# TSOC_RS485_EM.net
KiCad netlist of a schematic drawn in EAGLE
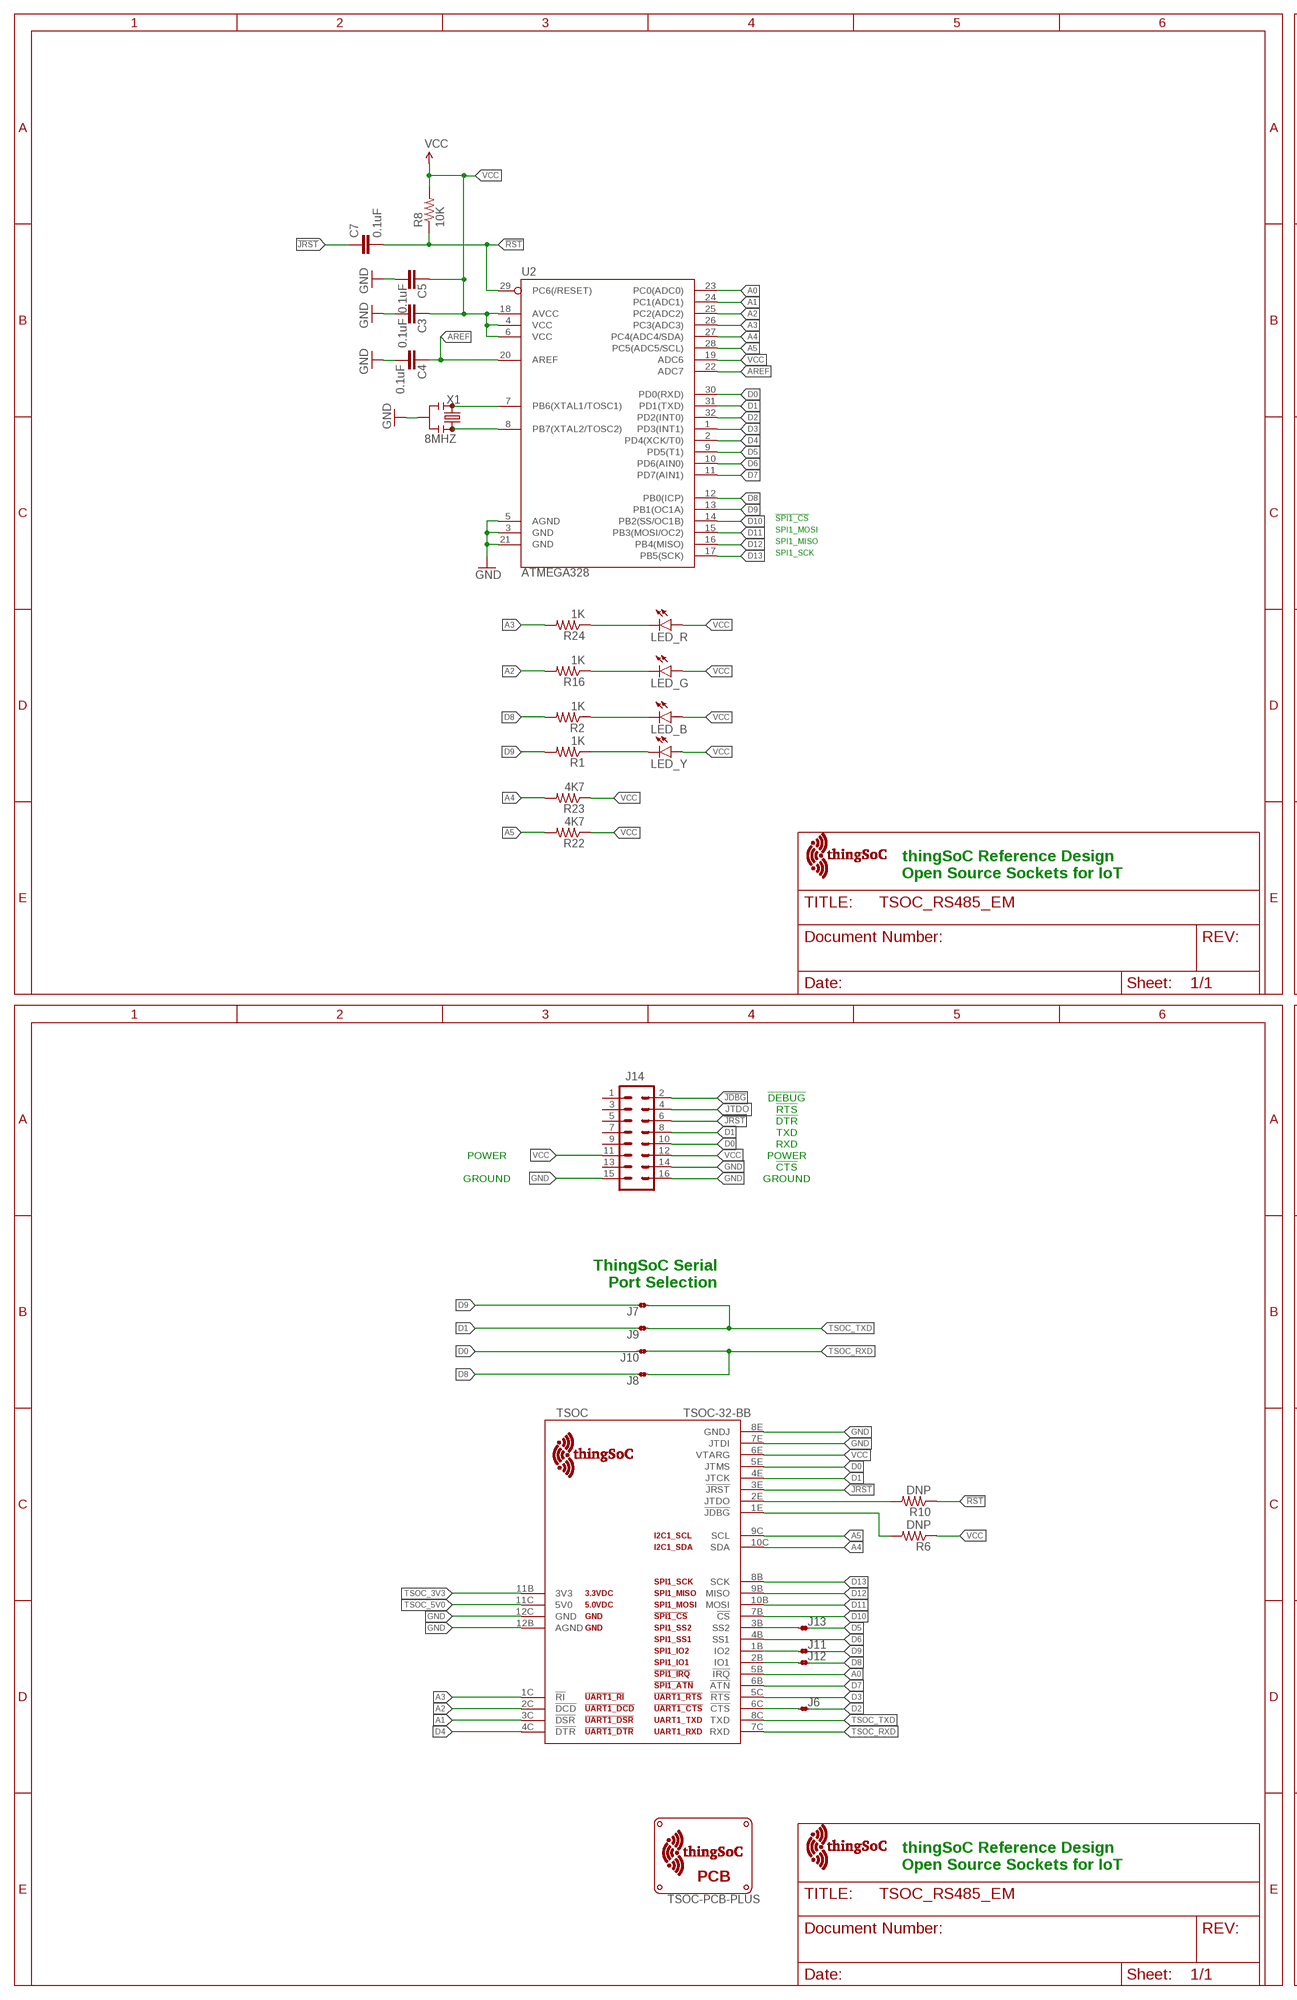
[diagram p0: schematic, sheet 1, part 1 of 2]
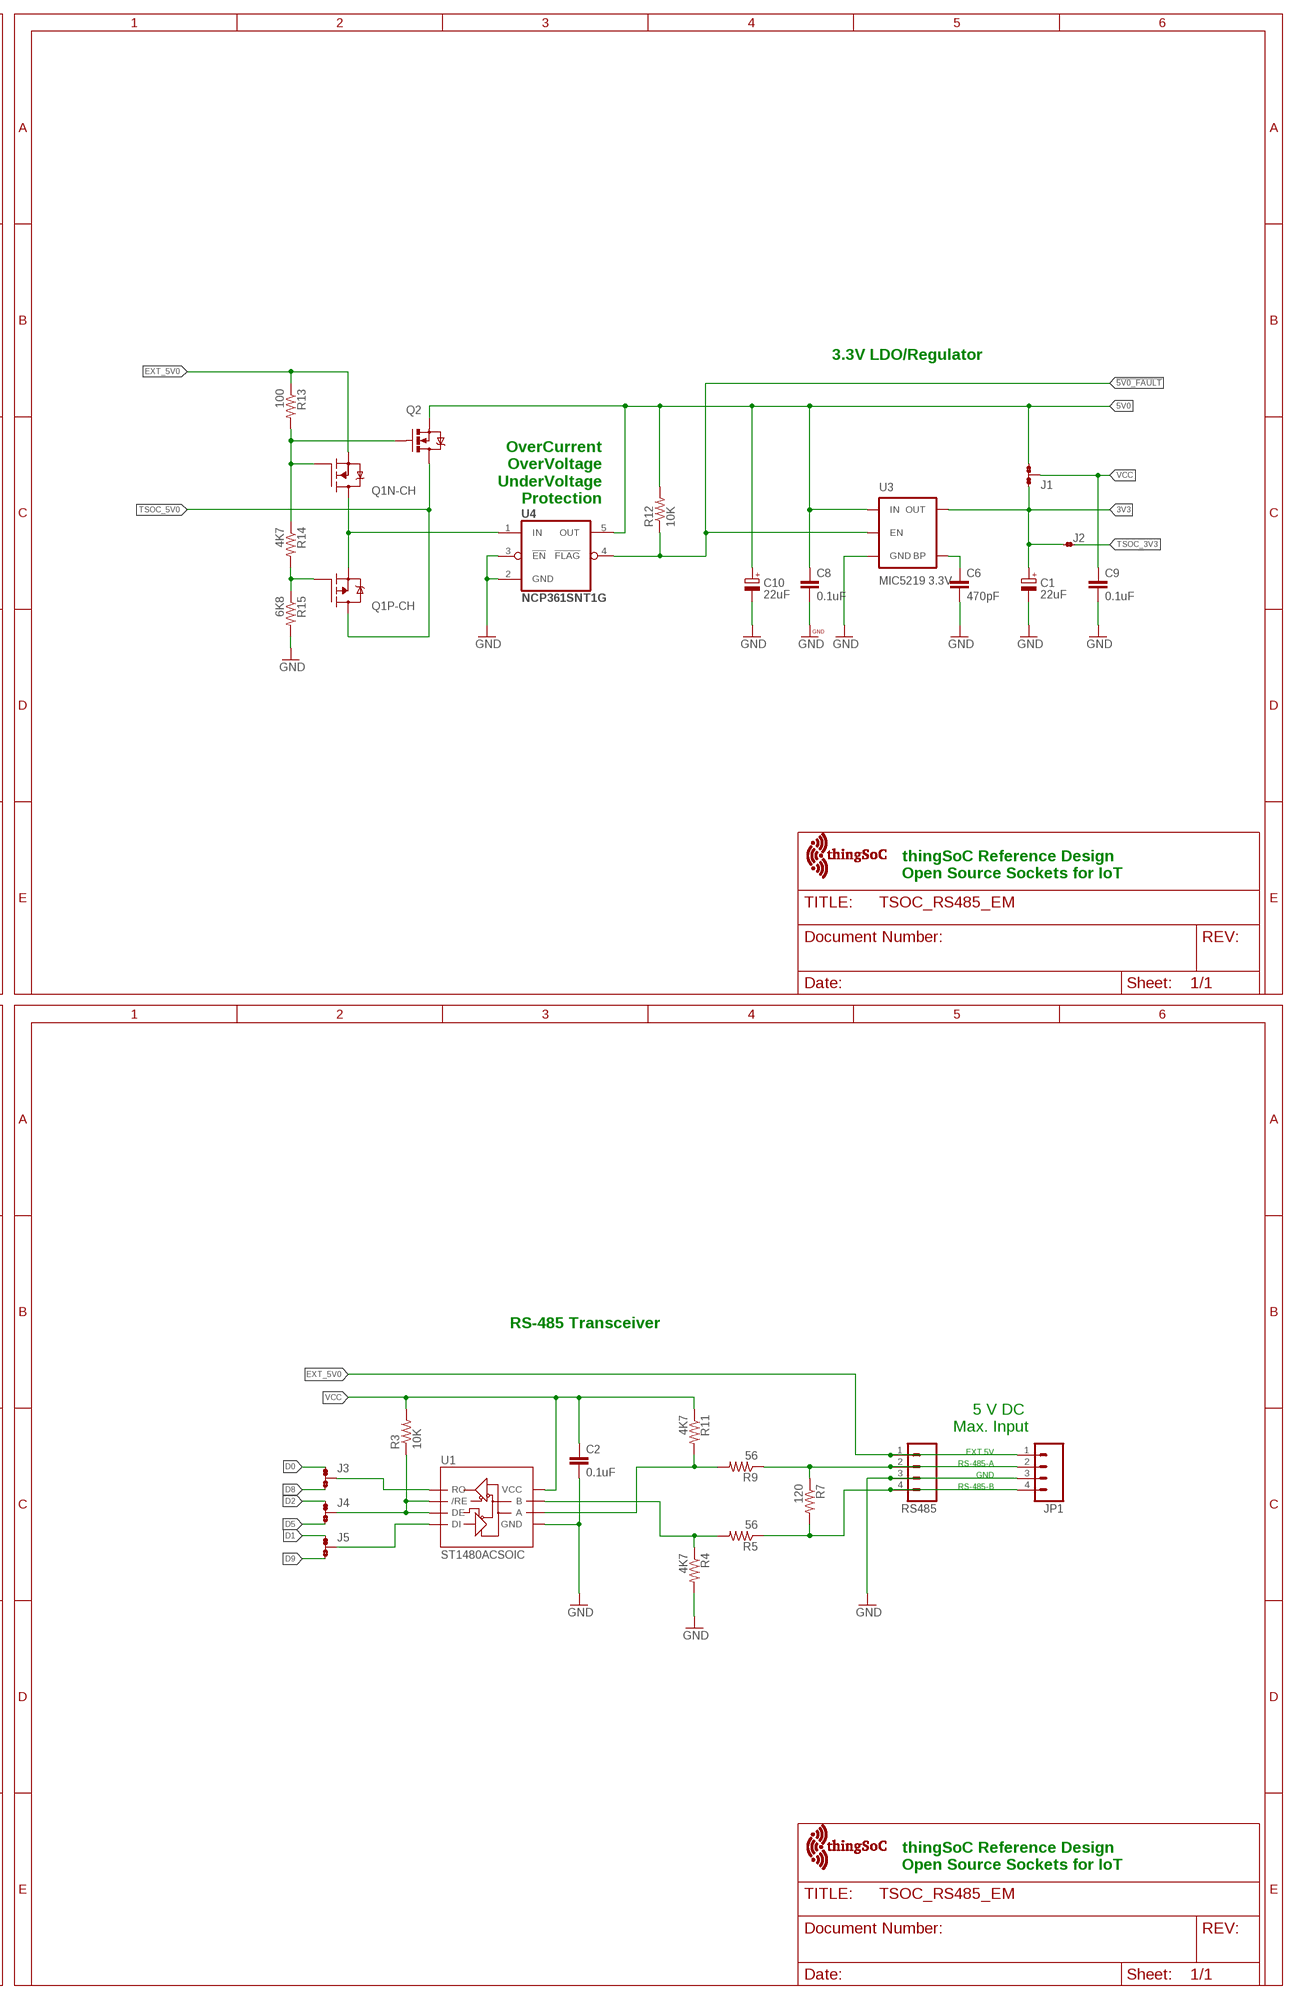
[diagram p1: schematic, sheet 1, part 2 of 2]

(export (version "E")
  (design (tool "Eeschema 10.0.6"))
  (components
    (comp (ref "C1")
      (value "22uF")
      (footprint "eagle-import:SMC_B")
      (libsource (lib "eagle-import") (part "CPOL-EUSMCB"))
    )
    (comp (ref "C2")
      (value "0.1uF")
      (footprint "eagle-import:EIA-0402")
      (libsource (lib "eagle-import") (part "CAPTYP"))
    )
    (comp (ref "C3")
      (value "0.1uF")
      (footprint "eagle-import:EIA-0402")
      (libsource (lib "eagle-import") (part "CAPTYP"))
    )
    (comp (ref "C4")
      (value "0.1uF")
      (footprint "eagle-import:EIA-0402")
      (libsource (lib "eagle-import") (part "CAPTYP"))
    )
    (comp (ref "C5")
      (value "0.1uF")
      (footprint "eagle-import:EIA-0402")
      (libsource (lib "eagle-import") (part "CAPTYP"))
    )
    (comp (ref "C6")
      (value "470pF")
      (footprint "eagle-import:EIA-0402")
      (libsource (lib "eagle-import") (part "CAPTYP"))
    )
    (comp (ref "C7")
      (value "0.1uF")
      (footprint "eagle-import:EIA-0402")
      (libsource (lib "eagle-import") (part "CAPTYP"))
    )
    (comp (ref "C8")
      (value "0.1uF")
      (footprint "eagle-import:EIA-0402")
      (libsource (lib "eagle-import") (part "CAPTYP"))
    )
    (comp (ref "C9")
      (value "0.1uF")
      (footprint "eagle-import:EIA-0402")
      (libsource (lib "eagle-import") (part "CAPTYP"))
    )
    (comp (ref "C10")
      (value "22uF")
      (footprint "eagle-import:SMC_B")
      (libsource (lib "eagle-import") (part "CPOL-EUSMCB"))
    )
    (comp (ref "J1")
      (value "JMP-3-1_2")
      (footprint "eagle-import:JMP-3-1_2")
      (libsource (lib "eagle-import") (part "JMP-3-1_2"))
    )
    (comp (ref "J2")
      (value "JMP-2-NC")
      (footprint "eagle-import:JMP-2-NC")
      (libsource (lib "eagle-import") (part "JMP-2-NC"))
    )
    (comp (ref "J3")
      (value "JMP-3-1_2")
      (footprint "eagle-import:JMP-3-1_2")
      (libsource (lib "eagle-import") (part "TSOC_RS485_EM_JMP-3-1_2"))
    )
    (comp (ref "J4")
      (value "JMP-3-1_2")
      (footprint "eagle-import:JMP-3-1_2")
      (libsource (lib "eagle-import") (part "TSOC_RS485_EM_JMP-3-1_2"))
    )
    (comp (ref "J5")
      (value "JMP-3-1_2")
      (footprint "eagle-import:JMP-3-1_2")
      (libsource (lib "eagle-import") (part "TSOC_RS485_EM_JMP-3-1_2"))
    )
    (comp (ref "J6")
      (value "JMP-2-NO")
      (footprint "eagle-import:JMP-2-NO")
      (libsource (lib "eagle-import") (part "JMP-2-NO"))
    )
    (comp (ref "J7")
      (value "JMP-2-NO")
      (footprint "eagle-import:JMP-2-NO")
      (libsource (lib "eagle-import") (part "JMP-2-NO"))
    )
    (comp (ref "J8")
      (value "JMP-2-NO")
      (footprint "eagle-import:JMP-2-NO")
      (libsource (lib "eagle-import") (part "JMP-2-NO"))
    )
    (comp (ref "J9")
      (value "JMP-2-NO")
      (footprint "eagle-import:JMP-2-NO")
      (libsource (lib "eagle-import") (part "JMP-2-NO"))
    )
    (comp (ref "J10")
      (value "JMP-2-NO")
      (footprint "eagle-import:JMP-2-NO")
      (libsource (lib "eagle-import") (part "JMP-2-NO"))
    )
    (comp (ref "J11")
      (value "JMP-2-NC")
      (footprint "eagle-import:JMP-2-NC")
      (libsource (lib "eagle-import") (part "JMP-2-NC"))
    )
    (comp (ref "J12")
      (value "JMP-2-NC")
      (footprint "eagle-import:JMP-2-NC")
      (libsource (lib "eagle-import") (part "JMP-2-NC"))
    )
    (comp (ref "J13")
      (value "JMP-2-NC")
      (footprint "eagle-import:JMP-2-NC")
      (libsource (lib "eagle-import") (part "JMP-2-NC"))
    )
    (comp (ref "J14")
      (value "M08X2")
      (footprint "eagle-import:2X8")
      (libsource (lib "eagle-import") (part "M08X2"))
    )
    (comp (ref "JP1")
      (value "M04PTH")
      (footprint "eagle-import:1X04")
      (libsource (lib "eagle-import") (part "M04PTH"))
    )
    (comp (ref "LED_B")
      (value "LED0603")
      (footprint "eagle-import:LED-0603")
      (libsource (lib "eagle-import") (part "LED0603"))
    )
    (comp (ref "LED_G")
      (value "LED0603")
      (footprint "eagle-import:LED-0603")
      (libsource (lib "eagle-import") (part "LED0603"))
    )
    (comp (ref "LED_R")
      (value "LED0603")
      (footprint "eagle-import:LED-0603")
      (libsource (lib "eagle-import") (part "LED0603"))
    )
    (comp (ref "LED_Y")
      (value "LED0603")
      (footprint "eagle-import:LED-0603")
      (libsource (lib "eagle-import") (part "LED0603"))
    )
    (comp (ref "Q1")
      (value "FDC6420C")
      (footprint "eagle-import:SOT95P280X110-6N")
      (libsource (lib "eagle-import") (part "FDC6420C"))
    )
    (comp (ref "Q2")
      (value "MOSFET-NCHANNELAO3404A")
      (footprint "eagle-import:SOT23-3")
      (libsource (lib "eagle-import") (part "MOSFET-NCHANNELAO3404A"))
    )
    (comp (ref "R1")
      (value "1K")
      (footprint "eagle-import:EIA-0402-MIN")
      (libsource (lib "eagle-import") (part "RESISTOR0402-MIN"))
    )
    (comp (ref "R2")
      (value "1K")
      (footprint "eagle-import:EIA-0402-MIN")
      (libsource (lib "eagle-import") (part "RESISTOR0402-MIN"))
    )
    (comp (ref "R3")
      (value "10K")
      (footprint "eagle-import:EIA-0402-MIN")
      (libsource (lib "eagle-import") (part "RESISTOR0402-MIN"))
    )
    (comp (ref "R4")
      (value "4K7")
      (footprint "eagle-import:EIA-0402-MIN")
      (libsource (lib "eagle-import") (part "RESISTOR0402-MIN"))
    )
    (comp (ref "R5")
      (value "56")
      (footprint "eagle-import:EIA-0402-MIN")
      (libsource (lib "eagle-import") (part "RESISTOR0402-MIN"))
    )
    (comp (ref "R6")
      (value "DNP")
      (footprint "eagle-import:EIA-0402-MIN")
      (libsource (lib "eagle-import") (part "RESISTOR0402-MIN"))
    )
    (comp (ref "R7")
      (value "120")
      (footprint "eagle-import:EIA-0402-MIN")
      (libsource (lib "eagle-import") (part "RESISTOR0402-MIN"))
    )
    (comp (ref "R8")
      (value "10K")
      (footprint "eagle-import:EIA-0402-MIN")
      (libsource (lib "eagle-import") (part "RESISTOR0402-MIN"))
    )
    (comp (ref "R9")
      (value "56")
      (footprint "eagle-import:EIA-0402-MIN")
      (libsource (lib "eagle-import") (part "RESISTOR0402-MIN"))
    )
    (comp (ref "R10")
      (value "DNP")
      (footprint "eagle-import:EIA-0402-MIN")
      (libsource (lib "eagle-import") (part "RESISTOR0402-MIN"))
    )
    (comp (ref "R11")
      (value "4K7")
      (footprint "eagle-import:EIA-0402-MIN")
      (libsource (lib "eagle-import") (part "RESISTOR0402-MIN"))
    )
    (comp (ref "R12")
      (value "10K")
      (footprint "eagle-import:EIA-0402-MIN")
      (libsource (lib "eagle-import") (part "RESISTOR0402-MIN"))
    )
    (comp (ref "R13")
      (value "100")
      (footprint "eagle-import:EIA-0402-MIN")
      (libsource (lib "eagle-import") (part "RESISTOR0402-MIN"))
    )
    (comp (ref "R14")
      (value "4K7")
      (footprint "eagle-import:EIA-0402-MIN")
      (libsource (lib "eagle-import") (part "RESISTOR0402-MIN"))
    )
    (comp (ref "R15")
      (value "6K8")
      (footprint "eagle-import:EIA-0402-MIN")
      (libsource (lib "eagle-import") (part "RESISTOR0402-MIN"))
    )
    (comp (ref "R16")
      (value "1K")
      (footprint "eagle-import:EIA-0402-MIN")
      (libsource (lib "eagle-import") (part "RESISTOR0402-MIN"))
    )
    (comp (ref "R22")
      (value "4K7")
      (footprint "eagle-import:EIA-0402-MIN")
      (libsource (lib "eagle-import") (part "RESISTOR0402-MIN"))
    )
    (comp (ref "R23")
      (value "4K7")
      (footprint "eagle-import:EIA-0402-MIN")
      (libsource (lib "eagle-import") (part "RESISTOR0402-MIN"))
    )
    (comp (ref "R24")
      (value "1K")
      (footprint "eagle-import:EIA-0402-MIN")
      (libsource (lib "eagle-import") (part "RESISTOR0402-MIN"))
    )
    (comp (ref "RS485")
      (value "M04SCREW")
      (footprint "eagle-import:SCREWTERMINAL-3.5MM-4")
      (libsource (lib "eagle-import") (part "M04SCREW"))
    )
    (comp (ref "TSOC")
      (value "TSOC-32-BB")
      (footprint "eagle-import:TSOC-BB-S32")
      (libsource (lib "eagle-import") (part "TSOC-32-BB"))
    )
    (comp (ref "U$3")
      (value "TSOC-PCB-PLUS")
      (footprint "eagle-import:TSOC-BB-BRD-PLUS")
      (libsource (lib "eagle-import") (part "TSOC-PCB-PLUS"))
    )
    (comp (ref "U$5")
      (value "TSOC-LOGO-SMALL")
      (footprint "eagle-import:TSOC-LOGO-SML")
      (libsource (lib "eagle-import") (part "TSOC-LOGO-SMALL"))
    )
    (comp (ref "U$6")
      (value "TSOC-LOGO-SMALL")
      (footprint "eagle-import:TSOC-LOGO-SML")
      (libsource (lib "eagle-import") (part "TSOC-LOGO-SMALL"))
    )
    (comp (ref "U$7")
      (value "TSOC-LOGO-SMALL")
      (footprint "eagle-import:TSOC-LOGO-SML")
      (libsource (lib "eagle-import") (part "TSOC-LOGO-SMALL"))
    )
    (comp (ref "U$8")
      (value "TSOC-LOGO-SMALL")
      (footprint "eagle-import:TSOC-LOGO-SML")
      (libsource (lib "eagle-import") (part "TSOC-LOGO-SMALL"))
    )
    (comp (ref "U1")
      (value "ST1480ACSOIC")
      (footprint "eagle-import:SO08")
      (libsource (lib "eagle-import") (part "ST1480ACSOIC"))
    )
    (comp (ref "U2")
      (value "ATMEGA328")
      (footprint "eagle-import:TQFP32-08")
      (libsource (lib "eagle-import") (part "ATMEGA168"))
    )
    (comp (ref "U3")
      (value "MIC5219 3.3V")
      (footprint "eagle-import:SOT23-5")
      (libsource (lib "eagle-import") (part "V_REG_MIC52193.3V"))
    )
    (comp (ref "U4")
      (value "NCP361SNT1G")
      (footprint "eagle-import:SOP95P275X110-5N")
      (libsource (lib "eagle-import") (part "NCP361SNT1G"))
    )
    (comp (ref "X1")
      (value "8MHZ")
      (footprint "eagle-import:RESONATOR-SMD")
      (libsource (lib "eagle-import") (part "RESONATOR8MHZ"))
    )
  )
  (nets
    (net (code "1") (name "/~{5V0_FAULT}") (class "Default")
      (node (ref "R12") (pin "1") (pinfunction "1_1") (pintype "passive"))
      (node (ref "U3") (pin "3") (pinfunction "EN_3") (pintype "input"))
      (node (ref "U4") (pin "4") (pinfunction "~{FLAG}_4") (pintype "input"))
    )
    (net (code "2") (name "/~{JDBG}") (class "Default")
      (node (ref "J14") (pin "2") (pinfunction "2_2") (pintype "passive"))
      (node (ref "R6") (pin "2") (pinfunction "2_2") (pintype "passive"))
      (node (ref "TSOC") (pin "1E") (pinfunction "~{JDBG}_1E") (pintype "bidirectional"))
    )
    (net (code "3") (name "/~{JRST}") (class "Default")
      (node (ref "C7") (pin "1") (pinfunction "1_1") (pintype "passive"))
      (node (ref "J14") (pin "6") (pinfunction "6_6") (pintype "passive"))
      (node (ref "TSOC") (pin "3E") (pinfunction "~{JRST}_3E") (pintype "bidirectional"))
    )
    (net (code "4") (name "/~{RST}") (class "Default")
      (node (ref "C7") (pin "2") (pinfunction "2_2") (pintype "passive"))
      (node (ref "R10") (pin "1") (pinfunction "1_1") (pintype "passive"))
      (node (ref "R8") (pin "1") (pinfunction "1_1") (pintype "passive"))
      (node (ref "U2") (pin "29") (pinfunction "PC6(/RESET)_29") (pintype "bidirectional"))
    )
    (net (code "5") (name "3V3") (class "Default")
      (node (ref "C1") (pin "+") (pinfunction "+_+") (pintype "passive"))
      (node (ref "J1") (pin "1") (pinfunction "1_1") (pintype "passive"))
      (node (ref "J2") (pin "1") (pinfunction "1_1") (pintype "passive"))
      (node (ref "U3") (pin "5") (pinfunction "OUT_5") (pintype "passive"))
    )
    (net (code "6") (name "5V0") (class "Default")
      (node (ref "C10") (pin "+") (pinfunction "+_+") (pintype "passive"))
      (node (ref "C8") (pin "1") (pinfunction "1_1") (pintype "passive"))
      (node (ref "J1") (pin "3") (pinfunction "3_3") (pintype "passive"))
      (node (ref "Q2") (pin "2") (pinfunction "S_2") (pintype "passive"))
      (node (ref "R12") (pin "2") (pinfunction "2_2") (pintype "passive"))
      (node (ref "U3") (pin "1") (pinfunction "IN_1") (pintype "input"))
      (node (ref "U4") (pin "5") (pinfunction "OUT_5") (pintype "output"))
    )
    (net (code "7") (name "A0") (class "Default")
      (node (ref "TSOC") (pin "5B") (pinfunction "~{IRQ}_5B") (pintype "bidirectional"))
      (node (ref "U2") (pin "23") (pinfunction "PC0(ADC0)_23") (pintype "bidirectional"))
    )
    (net (code "8") (name "A1") (class "Default")
      (node (ref "TSOC") (pin "3C") (pinfunction "~{DSR}_3C") (pintype "bidirectional"))
      (node (ref "U2") (pin "24") (pinfunction "PC1(ADC1)_24") (pintype "bidirectional"))
    )
    (net (code "9") (name "A2") (class "Default")
      (node (ref "R16") (pin "2") (pinfunction "2_2") (pintype "passive"))
      (node (ref "TSOC") (pin "2C") (pinfunction "~{DCD}_2C") (pintype "bidirectional"))
      (node (ref "U2") (pin "25") (pinfunction "PC2(ADC2)_25") (pintype "bidirectional"))
    )
    (net (code "10") (name "A3") (class "Default")
      (node (ref "R24") (pin "2") (pinfunction "2_2") (pintype "passive"))
      (node (ref "TSOC") (pin "1C") (pinfunction "~{RI}_1C") (pintype "bidirectional"))
      (node (ref "U2") (pin "26") (pinfunction "PC3(ADC3)_26") (pintype "bidirectional"))
    )
    (net (code "11") (name "A4") (class "Default")
      (node (ref "R23") (pin "2") (pinfunction "2_2") (pintype "passive"))
      (node (ref "TSOC") (pin "10C") (pinfunction "SDA_10C") (pintype "bidirectional"))
      (node (ref "U2") (pin "27") (pinfunction "PC4(ADC4/SDA)_27") (pintype "bidirectional"))
    )
    (net (code "12") (name "A5") (class "Default")
      (node (ref "R22") (pin "2") (pinfunction "2_2") (pintype "passive"))
      (node (ref "TSOC") (pin "9C") (pinfunction "SCL_9C") (pintype "bidirectional"))
      (node (ref "U2") (pin "28") (pinfunction "PC5(ADC5/SCL)_28") (pintype "bidirectional"))
    )
    (net (code "13") (name "AREF") (class "Default")
      (node (ref "C4") (pin "2") (pinfunction "2_2") (pintype "passive"))
      (node (ref "U2") (pin "20") (pinfunction "AREF_20") (pintype "bidirectional"))
      (node (ref "U2") (pin "22") (pinfunction "ADC7_22") (pintype "bidirectional"))
    )
    (net (code "14") (name "D0") (class "Default")
      (node (ref "J10") (pin "2") (pinfunction "2_2") (pintype "passive"))
      (node (ref "J14") (pin "10") (pinfunction "10_10") (pintype "passive"))
      (node (ref "J3") (pin "1") (pinfunction "1_1") (pintype "passive"))
      (node (ref "TSOC") (pin "5E") (pinfunction "JTMS_5E") (pintype "bidirectional"))
      (node (ref "U2") (pin "30") (pinfunction "PD0(RXD)_30") (pintype "bidirectional"))
    )
    (net (code "15") (name "D1") (class "Default")
      (node (ref "J14") (pin "8") (pinfunction "8_8") (pintype "passive"))
      (node (ref "J5") (pin "1") (pinfunction "1_1") (pintype "passive"))
      (node (ref "J9") (pin "2") (pinfunction "2_2") (pintype "passive"))
      (node (ref "TSOC") (pin "4E") (pinfunction "JTCK_4E") (pintype "bidirectional"))
      (node (ref "U2") (pin "31") (pinfunction "PD1(TXD)_31") (pintype "bidirectional"))
    )
    (net (code "16") (name "D2") (class "Default")
      (node (ref "J4") (pin "1") (pinfunction "1_1") (pintype "passive"))
      (node (ref "J6") (pin "2") (pinfunction "2_2") (pintype "passive"))
      (node (ref "U2") (pin "32") (pinfunction "PD2(INT0)_32") (pintype "bidirectional"))
    )
    (net (code "17") (name "D3") (class "Default")
      (node (ref "TSOC") (pin "5C") (pinfunction "~{RTS}_5C") (pintype "bidirectional"))
      (node (ref "U2") (pin "1") (pinfunction "PD3(INT1)_1") (pintype "bidirectional"))
    )
    (net (code "18") (name "D4") (class "Default")
      (node (ref "TSOC") (pin "4C") (pinfunction "~{DTR}_4C") (pintype "bidirectional"))
      (node (ref "U2") (pin "2") (pinfunction "PD4(XCK/T0)_2") (pintype "bidirectional"))
    )
    (net (code "19") (name "D5") (class "Default")
      (node (ref "J13") (pin "2") (pinfunction "2_2") (pintype "passive"))
      (node (ref "J4") (pin "3") (pinfunction "3_3") (pintype "passive"))
      (node (ref "U2") (pin "9") (pinfunction "PD5(T1)_9") (pintype "bidirectional"))
    )
    (net (code "20") (name "D6") (class "Default")
      (node (ref "TSOC") (pin "4B") (pinfunction "SS1_4B") (pintype "bidirectional"))
      (node (ref "U2") (pin "10") (pinfunction "PD6(AIN0)_10") (pintype "bidirectional"))
    )
    (net (code "21") (name "D7") (class "Default")
      (node (ref "TSOC") (pin "6B") (pinfunction "~{ATN}_6B") (pintype "bidirectional"))
      (node (ref "U2") (pin "11") (pinfunction "PD7(AIN1)_11") (pintype "bidirectional"))
    )
    (net (code "22") (name "D8") (class "Default")
      (node (ref "J12") (pin "2") (pinfunction "2_2") (pintype "passive"))
      (node (ref "J3") (pin "3") (pinfunction "3_3") (pintype "passive"))
      (node (ref "J8") (pin "2") (pinfunction "2_2") (pintype "passive"))
      (node (ref "R2") (pin "2") (pinfunction "2_2") (pintype "passive"))
      (node (ref "U2") (pin "12") (pinfunction "PB0(ICP)_12") (pintype "bidirectional"))
    )
    (net (code "23") (name "D9") (class "Default")
      (node (ref "J11") (pin "2") (pinfunction "2_2") (pintype "passive"))
      (node (ref "J5") (pin "3") (pinfunction "3_3") (pintype "passive"))
      (node (ref "J7") (pin "2") (pinfunction "2_2") (pintype "passive"))
      (node (ref "R1") (pin "2") (pinfunction "2_2") (pintype "passive"))
      (node (ref "U2") (pin "13") (pinfunction "PB1(OC1A)_13") (pintype "bidirectional"))
    )
    (net (code "24") (name "D10") (class "Default")
      (node (ref "TSOC") (pin "7B") (pinfunction "~{CS}_7B") (pintype "bidirectional"))
      (node (ref "U2") (pin "14") (pinfunction "PB2(SS/OC1B)_14") (pintype "bidirectional"))
    )
    (net (code "25") (name "D11") (class "Default")
      (node (ref "TSOC") (pin "10B") (pinfunction "MOSI_10B") (pintype "bidirectional"))
      (node (ref "U2") (pin "15") (pinfunction "PB3(MOSI/OC2)_15") (pintype "bidirectional"))
    )
    (net (code "26") (name "D12") (class "Default")
      (node (ref "TSOC") (pin "9B") (pinfunction "MISO_9B") (pintype "bidirectional"))
      (node (ref "U2") (pin "16") (pinfunction "PB4(MISO)_16") (pintype "bidirectional"))
    )
    (net (code "27") (name "D13") (class "Default")
      (node (ref "TSOC") (pin "8B") (pinfunction "SCK_8B") (pintype "bidirectional"))
      (node (ref "U2") (pin "17") (pinfunction "PB5(SCK)_17") (pintype "bidirectional"))
    )
    (net (code "28") (name "EXT_5V0") (class "Default")
      (node (ref "JP1") (pin "1") (pinfunction "1_1") (pintype "passive"))
      (node (ref "Q1") (pin "5") (pinfunction "S_5") (pintype "passive"))
      (node (ref "R13") (pin "1") (pinfunction "1_1") (pintype "passive"))
      (node (ref "RS485") (pin "1") (pinfunction "1_1") (pintype "passive"))
    )
    (net (code "29") (name "GND") (class "Default")
      (node (ref "C1") (pin "-") (pinfunction "-_-") (pintype "passive"))
      (node (ref "C10") (pin "-") (pinfunction "-_-") (pintype "passive"))
      (node (ref "C2") (pin "2") (pinfunction "2_2") (pintype "passive"))
      (node (ref "C3") (pin "1") (pinfunction "1_1") (pintype "passive"))
      (node (ref "C4") (pin "1") (pinfunction "1_1") (pintype "passive"))
      (node (ref "C5") (pin "1") (pinfunction "1_1") (pintype "passive"))
      (node (ref "C6") (pin "2") (pinfunction "2_2") (pintype "passive"))
      (node (ref "C8") (pin "2") (pinfunction "2_2") (pintype "passive"))
      (node (ref "C9") (pin "2") (pinfunction "2_2") (pintype "passive"))
      (node (ref "J14") (pin "14") (pinfunction "14_14") (pintype "passive"))
      (node (ref "J14") (pin "15") (pinfunction "15_15") (pintype "passive"))
      (node (ref "J14") (pin "16") (pinfunction "16_16") (pintype "passive"))
      (node (ref "JP1") (pin "3") (pinfunction "3_3") (pintype "passive"))
      (node (ref "R15") (pin "2") (pinfunction "2_2") (pintype "passive"))
      (node (ref "R4") (pin "2") (pinfunction "2_2") (pintype "passive"))
      (node (ref "RS485") (pin "3") (pinfunction "3_3") (pintype "passive"))
      (node (ref "TSOC") (pin "12B") (pinfunction "AGND_12B") (pintype "bidirectional"))
      (node (ref "TSOC") (pin "12C") (pinfunction "GND_12C") (pintype "bidirectional"))
      (node (ref "TSOC") (pin "7E") (pinfunction "JTDI_7E") (pintype "bidirectional"))
      (node (ref "TSOC") (pin "8E") (pinfunction "GNDJ_8E") (pintype "bidirectional"))
      (node (ref "U1") (pin "5") (pinfunction "GND_5") (pintype "bidirectional"))
      (node (ref "U2") (pin "21") (pinfunction "GND_21") (pintype "bidirectional"))
      (node (ref "U2") (pin "3") (pinfunction "GND_3") (pintype "bidirectional"))
      (node (ref "U2") (pin "5") (pinfunction "AGND_5") (pintype "bidirectional"))
      (node (ref "U3") (pin "2") (pinfunction "GND_2") (pintype "input"))
      (node (ref "U4") (pin "2") (pinfunction "GND_2") (pintype "passive"))
      (node (ref "U4") (pin "3") (pinfunction "~{EN}_3") (pintype "input"))
      (node (ref "X1") (pin "2") (pinfunction "2_2") (pintype "passive"))
    )
    (net (code "30") (name "JTDO") (class "Default")
      (node (ref "J14") (pin "4") (pinfunction "4_4") (pintype "passive"))
      (node (ref "R10") (pin "2") (pinfunction "2_2") (pintype "passive"))
      (node (ref "TSOC") (pin "2E") (pinfunction "JTDO_2E") (pintype "bidirectional"))
    )
    (net (code "31") (name "Net-(JP1-Pad2)") (class "Default")
      (node (ref "JP1") (pin "2") (pinfunction "2_2") (pintype "passive"))
      (node (ref "R7") (pin "1") (pinfunction "1_1") (pintype "passive"))
      (node (ref "R9") (pin "1") (pinfunction "1_1") (pintype "passive"))
      (node (ref "RS485") (pin "2") (pinfunction "2_2") (pintype "passive"))
    )
    (net (code "32") (name "Net-(JP1-Pad4)") (class "Default")
      (node (ref "JP1") (pin "4") (pinfunction "4_4") (pintype "passive"))
      (node (ref "R5") (pin "1") (pinfunction "1_1") (pintype "passive"))
      (node (ref "R7") (pin "2") (pinfunction "2_2") (pintype "passive"))
      (node (ref "RS485") (pin "4") (pinfunction "4_4") (pintype "passive"))
    )
    (net (code "33") (name "Net-(LED_B-PadC)") (class "Default")
      (node (ref "LED_B") (pin "C") (pinfunction "C_C") (pintype "passive"))
      (node (ref "R2") (pin "1") (pinfunction "1_1") (pintype "passive"))
    )
    (net (code "34") (name "Net-(LED_G-PadC)") (class "Default")
      (node (ref "LED_G") (pin "C") (pinfunction "C_C") (pintype "passive"))
      (node (ref "R16") (pin "1") (pinfunction "1_1") (pintype "passive"))
    )
    (net (code "35") (name "Net-(LED_R-PadC)") (class "Default")
      (node (ref "LED_R") (pin "C") (pinfunction "C_C") (pintype "passive"))
      (node (ref "R24") (pin "1") (pinfunction "1_1") (pintype "passive"))
    )
    (net (code "36") (name "Net-(LED_Y-PadC)") (class "Default")
      (node (ref "LED_Y") (pin "C") (pinfunction "C_C") (pintype "passive"))
      (node (ref "R1") (pin "1") (pinfunction "1_1") (pintype "passive"))
    )
    (net (code "37") (name "Net-(Q1A-D)") (class "Default")
      (node (ref "Q1") (pin "2") (pinfunction "S_2") (pintype "passive"))
      (node (ref "Q1") (pin "6") (pinfunction "D_6") (pintype "passive"))
      (node (ref "U4") (pin "1") (pinfunction "IN_1") (pintype "power_in"))
    )
    (net (code "38") (name "Net-(Q1A-G)") (class "Default")
      (node (ref "Q1") (pin "1") (pinfunction "G_1") (pintype "passive"))
      (node (ref "Q2") (pin "1") (pinfunction "G_1") (pintype "passive"))
      (node (ref "R13") (pin "2") (pinfunction "2_2") (pintype "passive"))
      (node (ref "R14") (pin "1") (pinfunction "1_1") (pintype "passive"))
    )
    (net (code "39") (name "Net-(Q1B-G)") (class "Default")
      (node (ref "Q1") (pin "3") (pinfunction "G_3") (pintype "passive"))
      (node (ref "R14") (pin "2") (pinfunction "2_2") (pintype "passive"))
      (node (ref "R15") (pin "1") (pinfunction "1_1") (pintype "passive"))
    )
    (net (code "40") (name "Net-(TSOC-IO1)") (class "Default")
      (node (ref "J12") (pin "1") (pinfunction "1_1") (pintype "passive"))
      (node (ref "TSOC") (pin "2B") (pinfunction "IO1_2B") (pintype "bidirectional"))
    )
    (net (code "41") (name "Net-(TSOC-IO2)") (class "Default")
      (node (ref "J11") (pin "1") (pinfunction "1_1") (pintype "passive"))
      (node (ref "TSOC") (pin "1B") (pinfunction "IO2_1B") (pintype "bidirectional"))
    )
    (net (code "42") (name "Net-(TSOC-SS2)") (class "Default")
      (node (ref "J13") (pin "1") (pinfunction "1_1") (pintype "passive"))
      (node (ref "TSOC") (pin "3B") (pinfunction "SS2_3B") (pintype "bidirectional"))
    )
    (net (code "43") (name "Net-(TSOC-~{CTS})") (class "Default")
      (node (ref "J6") (pin "1") (pinfunction "1_1") (pintype "passive"))
      (node (ref "TSOC") (pin "6C") (pinfunction "~{CTS}_6C") (pintype "bidirectional"))
    )
    (net (code "44") (name "Net-(U1-A)") (class "Default")
      (node (ref "R11") (pin "2") (pinfunction "2_2") (pintype "passive"))
      (node (ref "R9") (pin "2") (pinfunction "2_2") (pintype "passive"))
      (node (ref "U1") (pin "6") (pinfunction "A_6") (pintype "bidirectional"))
    )
    (net (code "45") (name "Net-(U1-B)") (class "Default")
      (node (ref "R4") (pin "1") (pinfunction "1_1") (pintype "passive"))
      (node (ref "R5") (pin "2") (pinfunction "2_2") (pintype "passive"))
      (node (ref "U1") (pin "7") (pinfunction "B_7") (pintype "bidirectional"))
    )
    (net (code "46") (name "Net-(U1-DE)") (class "Default")
      (node (ref "J4") (pin "2") (pinfunction "2_2") (pintype "passive"))
      (node (ref "R3") (pin "1") (pinfunction "1_1") (pintype "passive"))
      (node (ref "U1") (pin "2") (pinfunction "/RE_2") (pintype "bidirectional"))
      (node (ref "U1") (pin "3") (pinfunction "DE_3") (pintype "bidirectional"))
    )
    (net (code "47") (name "Net-(U1-DI)") (class "Default")
      (node (ref "J5") (pin "2") (pinfunction "2_2") (pintype "passive"))
      (node (ref "U1") (pin "4") (pinfunction "DI_4") (pintype "bidirectional"))
    )
    (net (code "48") (name "Net-(U1-RO)") (class "Default")
      (node (ref "J3") (pin "2") (pinfunction "2_2") (pintype "passive"))
      (node (ref "U1") (pin "1") (pinfunction "RO_1") (pintype "bidirectional"))
    )
    (net (code "49") (name "Net-(U2-PB6(XTAL1{slash}TOSC1))") (class "Default")
      (node (ref "U2") (pin "7") (pinfunction "PB6(XTAL1/TOSC1)_7") (pintype "bidirectional"))
      (node (ref "X1") (pin "3") (pinfunction "3_3") (pintype "passive"))
    )
    (net (code "50") (name "Net-(U2-PB7(XTAL2{slash}TOSC2))") (class "Default")
      (node (ref "U2") (pin "8") (pinfunction "PB7(XTAL2/TOSC2)_8") (pintype "bidirectional"))
      (node (ref "X1") (pin "1") (pinfunction "1_1") (pintype "passive"))
    )
    (net (code "51") (name "Net-(U3-BP)") (class "Default")
      (node (ref "C6") (pin "1") (pinfunction "1_1") (pintype "passive"))
      (node (ref "U3") (pin "4") (pinfunction "BP_4") (pintype "input"))
    )
    (net (code "52") (name "TSOC_3V3") (class "Default")
      (node (ref "J2") (pin "2") (pinfunction "2_2") (pintype "passive"))
      (node (ref "TSOC") (pin "11B") (pinfunction "3V3_11B") (pintype "bidirectional"))
    )
    (net (code "53") (name "TSOC_5V0") (class "Default")
      (node (ref "Q1") (pin "4") (pinfunction "D_4") (pintype "passive"))
      (node (ref "Q2") (pin "3") (pinfunction "D_3") (pintype "passive"))
      (node (ref "TSOC") (pin "11C") (pinfunction "5V0_11C") (pintype "bidirectional"))
    )
    (net (code "54") (name "TSOC_RXD") (class "Default")
      (node (ref "J10") (pin "1") (pinfunction "1_1") (pintype "passive"))
      (node (ref "J8") (pin "1") (pinfunction "1_1") (pintype "passive"))
      (node (ref "TSOC") (pin "7C") (pinfunction "RXD_7C") (pintype "bidirectional"))
    )
    (net (code "55") (name "TSOC_TXD") (class "Default")
      (node (ref "J7") (pin "1") (pinfunction "1_1") (pintype "passive"))
      (node (ref "J9") (pin "1") (pinfunction "1_1") (pintype "passive"))
      (node (ref "TSOC") (pin "8C") (pinfunction "TXD_8C") (pintype "bidirectional"))
    )
    (net (code "56") (name "VCC") (class "Default")
      (node (ref "C2") (pin "1") (pinfunction "1_1") (pintype "passive"))
      (node (ref "C3") (pin "2") (pinfunction "2_2") (pintype "passive"))
      (node (ref "C5") (pin "2") (pinfunction "2_2") (pintype "passive"))
      (node (ref "C9") (pin "1") (pinfunction "1_1") (pintype "passive"))
      (node (ref "J1") (pin "2") (pinfunction "2_2") (pintype "passive"))
      (node (ref "J14") (pin "11") (pinfunction "11_11") (pintype "passive"))
      (node (ref "J14") (pin "12") (pinfunction "12_12") (pintype "passive"))
      (node (ref "LED_B") (pin "A") (pinfunction "A_A") (pintype "passive"))
      (node (ref "LED_G") (pin "A") (pinfunction "A_A") (pintype "passive"))
      (node (ref "LED_R") (pin "A") (pinfunction "A_A") (pintype "passive"))
      (node (ref "LED_Y") (pin "A") (pinfunction "A_A") (pintype "passive"))
      (node (ref "R11") (pin "1") (pinfunction "1_1") (pintype "passive"))
      (node (ref "R22") (pin "1") (pinfunction "1_1") (pintype "passive"))
      (node (ref "R23") (pin "1") (pinfunction "1_1") (pintype "passive"))
      (node (ref "R3") (pin "2") (pinfunction "2_2") (pintype "passive"))
      (node (ref "R6") (pin "1") (pinfunction "1_1") (pintype "passive"))
      (node (ref "R8") (pin "2") (pinfunction "2_2") (pintype "passive"))
      (node (ref "TSOC") (pin "6E") (pinfunction "VTARG_6E") (pintype "bidirectional"))
      (node (ref "U1") (pin "8") (pinfunction "VCC_8") (pintype "bidirectional"))
      (node (ref "U2") (pin "18") (pinfunction "AVCC_18") (pintype "bidirectional"))
      (node (ref "U2") (pin "19") (pinfunction "ADC6_19") (pintype "bidirectional"))
      (node (ref "U2") (pin "4") (pinfunction "VCC_4") (pintype "bidirectional"))
      (node (ref "U2") (pin "6") (pinfunction "VCC_6") (pintype "bidirectional"))
    )
    (net (code "57") (name "unconnected-(J14-Pad1)") (class "Default")
      (node (ref "J14") (pin "1") (pinfunction "1_1") (pintype "passive"))
    )
    (net (code "58") (name "unconnected-(J14-Pad3)") (class "Default")
      (node (ref "J14") (pin "3") (pinfunction "3_3") (pintype "passive"))
    )
    (net (code "59") (name "unconnected-(J14-Pad5)") (class "Default")
      (node (ref "J14") (pin "5") (pinfunction "5_5") (pintype "passive"))
    )
    (net (code "60") (name "unconnected-(J14-Pad7)") (class "Default")
      (node (ref "J14") (pin "7") (pinfunction "7_7") (pintype "passive"))
    )
    (net (code "61") (name "unconnected-(J14-Pad9)") (class "Default")
      (node (ref "J14") (pin "9") (pinfunction "9_9") (pintype "passive"))
    )
    (net (code "62") (name "unconnected-(J14-Pad13)") (class "Default")
      (node (ref "J14") (pin "13") (pinfunction "13_13") (pintype "passive"))
    )
  )
)
